# KEY.net
KiCad netlist of a schematic drawn in Altium Designer
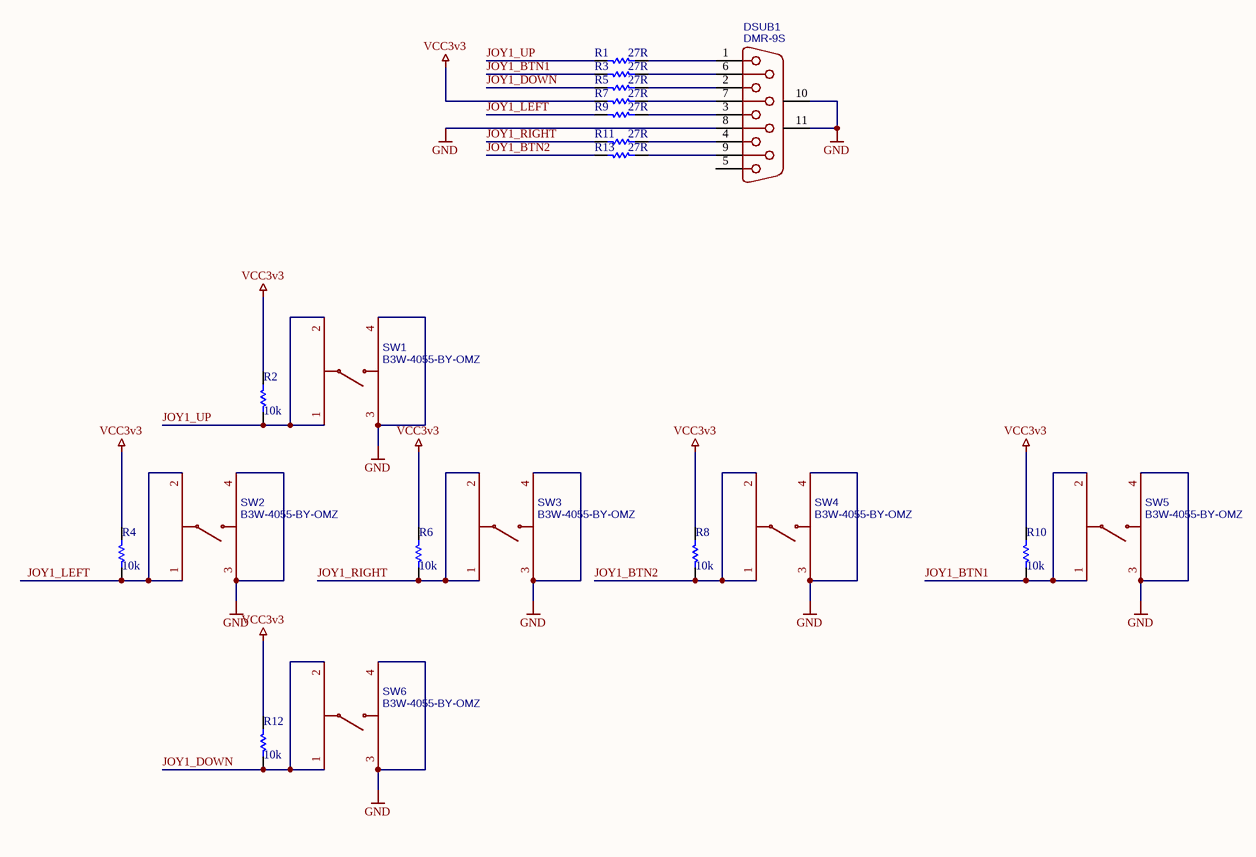
[diagram p0: KEY.SchDoc]

(export (version "E")
  (design (tool "Eeschema 10.0.6"))
  (components
    (comp (ref "DSUB1")
      (value "DMR-9S")
      (footprint "DSUB-TH_DMR-9S")
      (fields (field (name "BOM_SUPPLIER PART") "C141882") (field (name "CONTRIBUTOR") "LCSC"))
      (libsource (lib "altium-import") (part "root_0_DMR-9S_"))
    )
    (comp (ref "R1")
      (value "27R")
      (footprint "0603")
      (description "0603 footprint resistor")
      (fields (field (name "Comment") "0603"))
      (libsource (lib "Integrated Comp_lib") (part "RES_0603"))
    )
    (comp (ref "R2")
      (value "10k")
      (footprint "0603")
      (description "0603 footprint resistor")
      (fields (field (name "Comment") "0603"))
      (libsource (lib "Integrated Comp_lib") (part "RES_0603"))
    )
    (comp (ref "R3")
      (value "27R")
      (footprint "0603")
      (description "0603 footprint resistor")
      (fields (field (name "Comment") "0603"))
      (libsource (lib "Integrated Comp_lib") (part "RES_0603"))
    )
    (comp (ref "R4")
      (value "10k")
      (footprint "0603")
      (description "0603 footprint resistor")
      (fields (field (name "Comment") "0603"))
      (libsource (lib "Integrated Comp_lib") (part "RES_0603"))
    )
    (comp (ref "R5")
      (value "27R")
      (footprint "0603")
      (description "0603 footprint resistor")
      (fields (field (name "Comment") "0603"))
      (libsource (lib "Integrated Comp_lib") (part "RES_0603"))
    )
    (comp (ref "R6")
      (value "10k")
      (footprint "0603")
      (description "0603 footprint resistor")
      (fields (field (name "Comment") "0603"))
      (libsource (lib "Integrated Comp_lib") (part "RES_0603"))
    )
    (comp (ref "R7")
      (value "27R")
      (footprint "0603")
      (description "0603 footprint resistor")
      (fields (field (name "Comment") "0603"))
      (libsource (lib "Integrated Comp_lib") (part "RES_0603"))
    )
    (comp (ref "R8")
      (value "10k")
      (footprint "0603")
      (description "0603 footprint resistor")
      (fields (field (name "Comment") "0603"))
      (libsource (lib "Integrated Comp_lib") (part "RES_0603"))
    )
    (comp (ref "R9")
      (value "27R")
      (footprint "0603")
      (description "0603 footprint resistor")
      (fields (field (name "Comment") "0603"))
      (libsource (lib "Integrated Comp_lib") (part "RES_0603"))
    )
    (comp (ref "R10")
      (value "10k")
      (footprint "0603")
      (description "0603 footprint resistor")
      (fields (field (name "Comment") "0603"))
      (libsource (lib "Integrated Comp_lib") (part "RES_0603"))
    )
    (comp (ref "R11")
      (value "27R")
      (footprint "0603")
      (description "0603 footprint resistor")
      (fields (field (name "Comment") "0603"))
      (libsource (lib "Integrated Comp_lib") (part "RES_0603"))
    )
    (comp (ref "R12")
      (value "10k")
      (footprint "0603")
      (description "0603 footprint resistor")
      (fields (field (name "Comment") "0603"))
      (libsource (lib "Integrated Comp_lib") (part "RES_0603"))
    )
    (comp (ref "R13")
      (value "27R")
      (footprint "0603")
      (description "0603 footprint resistor")
      (fields (field (name "Comment") "0603"))
      (libsource (lib "Integrated Comp_lib") (part "RES_0603"))
    )
    (comp (ref "SW1")
      (value "B3W-4055-BY-OMZ")
      (footprint "SW-TH_4P-L12.0-W12.0-P5.00-LS12.5-EH")
      (fields (field (name "BOM_SUPPLIER PART") "C231334") (field (name "CONTRIBUTOR") "LCSC"))
      (libsource (lib "altium-import") (part "root_3_B3W-4055-BY-OMZ_"))
    )
    (comp (ref "SW2")
      (value "B3W-4055-BY-OMZ")
      (footprint "SW-TH_4P-L12.0-W12.0-P5.00-LS12.5-EH")
      (fields (field (name "BOM_SUPPLIER PART") "C231334") (field (name "CONTRIBUTOR") "LCSC"))
      (libsource (lib "altium-import") (part "root_3_B3W-4055-BY-OMZ_"))
    )
    (comp (ref "SW3")
      (value "B3W-4055-BY-OMZ")
      (footprint "SW-TH_4P-L12.0-W12.0-P5.00-LS12.5-EH")
      (fields (field (name "BOM_SUPPLIER PART") "C231334") (field (name "CONTRIBUTOR") "LCSC"))
      (libsource (lib "altium-import") (part "root_3_B3W-4055-BY-OMZ_"))
    )
    (comp (ref "SW4")
      (value "B3W-4055-BY-OMZ")
      (footprint "SW-TH_4P-L12.0-W12.0-P5.00-LS12.5-EH")
      (fields (field (name "BOM_SUPPLIER PART") "C231334") (field (name "CONTRIBUTOR") "LCSC"))
      (libsource (lib "altium-import") (part "root_3_B3W-4055-BY-OMZ_"))
    )
    (comp (ref "SW5")
      (value "B3W-4055-BY-OMZ")
      (footprint "SW-TH_4P-L12.0-W12.0-P5.00-LS12.5-EH")
      (fields (field (name "BOM_SUPPLIER PART") "C231334") (field (name "CONTRIBUTOR") "LCSC"))
      (libsource (lib "altium-import") (part "root_3_B3W-4055-BY-OMZ_"))
    )
    (comp (ref "SW6")
      (value "B3W-4055-BY-OMZ")
      (footprint "SW-TH_4P-L12.0-W12.0-P5.00-LS12.5-EH")
      (fields (field (name "BOM_SUPPLIER PART") "C231334") (field (name "CONTRIBUTOR") "LCSC"))
      (libsource (lib "altium-import") (part "root_3_B3W-4055-BY-OMZ_"))
    )
  )
  (nets
    (net (code "1") (name "/JOY1_BTN1") (class "Default")
      (node (ref "R10") (pin "2") (pinfunction "2_2") (pintype "passive"))
      (node (ref "R3") (pin "2") (pinfunction "2_2") (pintype "passive"))
      (node (ref "SW5") (pin "1") (pinfunction "1_1") (pintype "passive"))
      (node (ref "SW5") (pin "2") (pinfunction "2_2") (pintype "passive"))
    )
    (net (code "2") (name "/JOY1_BTN2") (class "Default")
      (node (ref "R13") (pin "2") (pinfunction "2_2") (pintype "passive"))
      (node (ref "R8") (pin "2") (pinfunction "2_2") (pintype "passive"))
      (node (ref "SW4") (pin "1") (pinfunction "1_1") (pintype "passive"))
      (node (ref "SW4") (pin "2") (pinfunction "2_2") (pintype "passive"))
    )
    (net (code "3") (name "/JOY1_DOWN") (class "Default")
      (node (ref "R12") (pin "2") (pinfunction "2_2") (pintype "passive"))
      (node (ref "R5") (pin "2") (pinfunction "2_2") (pintype "passive"))
      (node (ref "SW6") (pin "1") (pinfunction "1_1") (pintype "passive"))
      (node (ref "SW6") (pin "2") (pinfunction "2_2") (pintype "passive"))
    )
    (net (code "4") (name "/JOY1_LEFT") (class "Default")
      (node (ref "R4") (pin "2") (pinfunction "2_2") (pintype "passive"))
      (node (ref "R9") (pin "2") (pinfunction "2_2") (pintype "passive"))
      (node (ref "SW2") (pin "1") (pinfunction "1_1") (pintype "passive"))
      (node (ref "SW2") (pin "2") (pinfunction "2_2") (pintype "passive"))
    )
    (net (code "5") (name "/JOY1_RIGHT") (class "Default")
      (node (ref "R11") (pin "2") (pinfunction "2_2") (pintype "passive"))
      (node (ref "R6") (pin "2") (pinfunction "2_2") (pintype "passive"))
      (node (ref "SW3") (pin "1") (pinfunction "1_1") (pintype "passive"))
      (node (ref "SW3") (pin "2") (pinfunction "2_2") (pintype "passive"))
    )
    (net (code "6") (name "/JOY1_UP") (class "Default")
      (node (ref "R1") (pin "2") (pinfunction "2_2") (pintype "passive"))
      (node (ref "R2") (pin "2") (pinfunction "2_2") (pintype "passive"))
      (node (ref "SW1") (pin "1") (pinfunction "1_1") (pintype "passive"))
      (node (ref "SW1") (pin "2") (pinfunction "2_2") (pintype "passive"))
    )
    (net (code "7") (name "GND") (class "Default")
      (node (ref "DSUB1") (pin "10") (pinfunction "MH1_10") (pintype "passive"))
      (node (ref "DSUB1") (pin "11") (pinfunction "MH2_11") (pintype "passive"))
      (node (ref "DSUB1") (pin "8") (pinfunction "8_8") (pintype "passive"))
      (node (ref "SW1") (pin "3") (pinfunction "3_3") (pintype "passive"))
      (node (ref "SW1") (pin "4") (pinfunction "4_4") (pintype "passive"))
      (node (ref "SW2") (pin "3") (pinfunction "3_3") (pintype "passive"))
      (node (ref "SW2") (pin "4") (pinfunction "4_4") (pintype "passive"))
      (node (ref "SW3") (pin "3") (pinfunction "3_3") (pintype "passive"))
      (node (ref "SW3") (pin "4") (pinfunction "4_4") (pintype "passive"))
      (node (ref "SW4") (pin "3") (pinfunction "3_3") (pintype "passive"))
      (node (ref "SW4") (pin "4") (pinfunction "4_4") (pintype "passive"))
      (node (ref "SW5") (pin "3") (pinfunction "3_3") (pintype "passive"))
      (node (ref "SW5") (pin "4") (pinfunction "4_4") (pintype "passive"))
      (node (ref "SW6") (pin "3") (pinfunction "3_3") (pintype "passive"))
      (node (ref "SW6") (pin "4") (pinfunction "4_4") (pintype "passive"))
    )
    (net (code "8") (name "Net-(DSUB1-Pad1)") (class "Default")
      (node (ref "DSUB1") (pin "1") (pinfunction "1_1") (pintype "passive"))
      (node (ref "R1") (pin "1") (pinfunction "1_1") (pintype "passive"))
    )
    (net (code "9") (name "Net-(DSUB1-Pad2)") (class "Default")
      (node (ref "DSUB1") (pin "2") (pinfunction "2_2") (pintype "passive"))
      (node (ref "R5") (pin "1") (pinfunction "1_1") (pintype "passive"))
    )
    (net (code "10") (name "Net-(DSUB1-Pad3)") (class "Default")
      (node (ref "DSUB1") (pin "3") (pinfunction "3_3") (pintype "passive"))
      (node (ref "R9") (pin "1") (pinfunction "1_1") (pintype "passive"))
    )
    (net (code "11") (name "Net-(DSUB1-Pad4)") (class "Default")
      (node (ref "DSUB1") (pin "4") (pinfunction "4_4") (pintype "passive"))
      (node (ref "R11") (pin "1") (pinfunction "1_1") (pintype "passive"))
    )
    (net (code "12") (name "Net-(DSUB1-Pad6)") (class "Default")
      (node (ref "DSUB1") (pin "6") (pinfunction "6_6") (pintype "passive"))
      (node (ref "R3") (pin "1") (pinfunction "1_1") (pintype "passive"))
    )
    (net (code "13") (name "Net-(DSUB1-Pad7)") (class "Default")
      (node (ref "DSUB1") (pin "7") (pinfunction "7_7") (pintype "passive"))
      (node (ref "R7") (pin "1") (pinfunction "1_1") (pintype "passive"))
    )
    (net (code "14") (name "Net-(DSUB1-Pad9)") (class "Default")
      (node (ref "DSUB1") (pin "9") (pinfunction "9_9") (pintype "passive"))
      (node (ref "R13") (pin "1") (pinfunction "1_1") (pintype "passive"))
    )
    (net (code "15") (name "VCC3v3") (class "Default")
      (node (ref "R10") (pin "1") (pinfunction "1_1") (pintype "passive"))
      (node (ref "R12") (pin "1") (pinfunction "1_1") (pintype "passive"))
      (node (ref "R2") (pin "1") (pinfunction "1_1") (pintype "passive"))
      (node (ref "R4") (pin "1") (pinfunction "1_1") (pintype "passive"))
      (node (ref "R6") (pin "1") (pinfunction "1_1") (pintype "passive"))
      (node (ref "R7") (pin "2") (pinfunction "2_2") (pintype "passive"))
      (node (ref "R8") (pin "1") (pinfunction "1_1") (pintype "passive"))
    )
    (net (code "16") (name "unconnected-(DSUB1-Pad5)") (class "Default")
      (node (ref "DSUB1") (pin "5") (pinfunction "5_5") (pintype "passive"))
    )
  )
)
